# usbshare_0_2.net
KiCad netlist of a schematic drawn in EAGLE
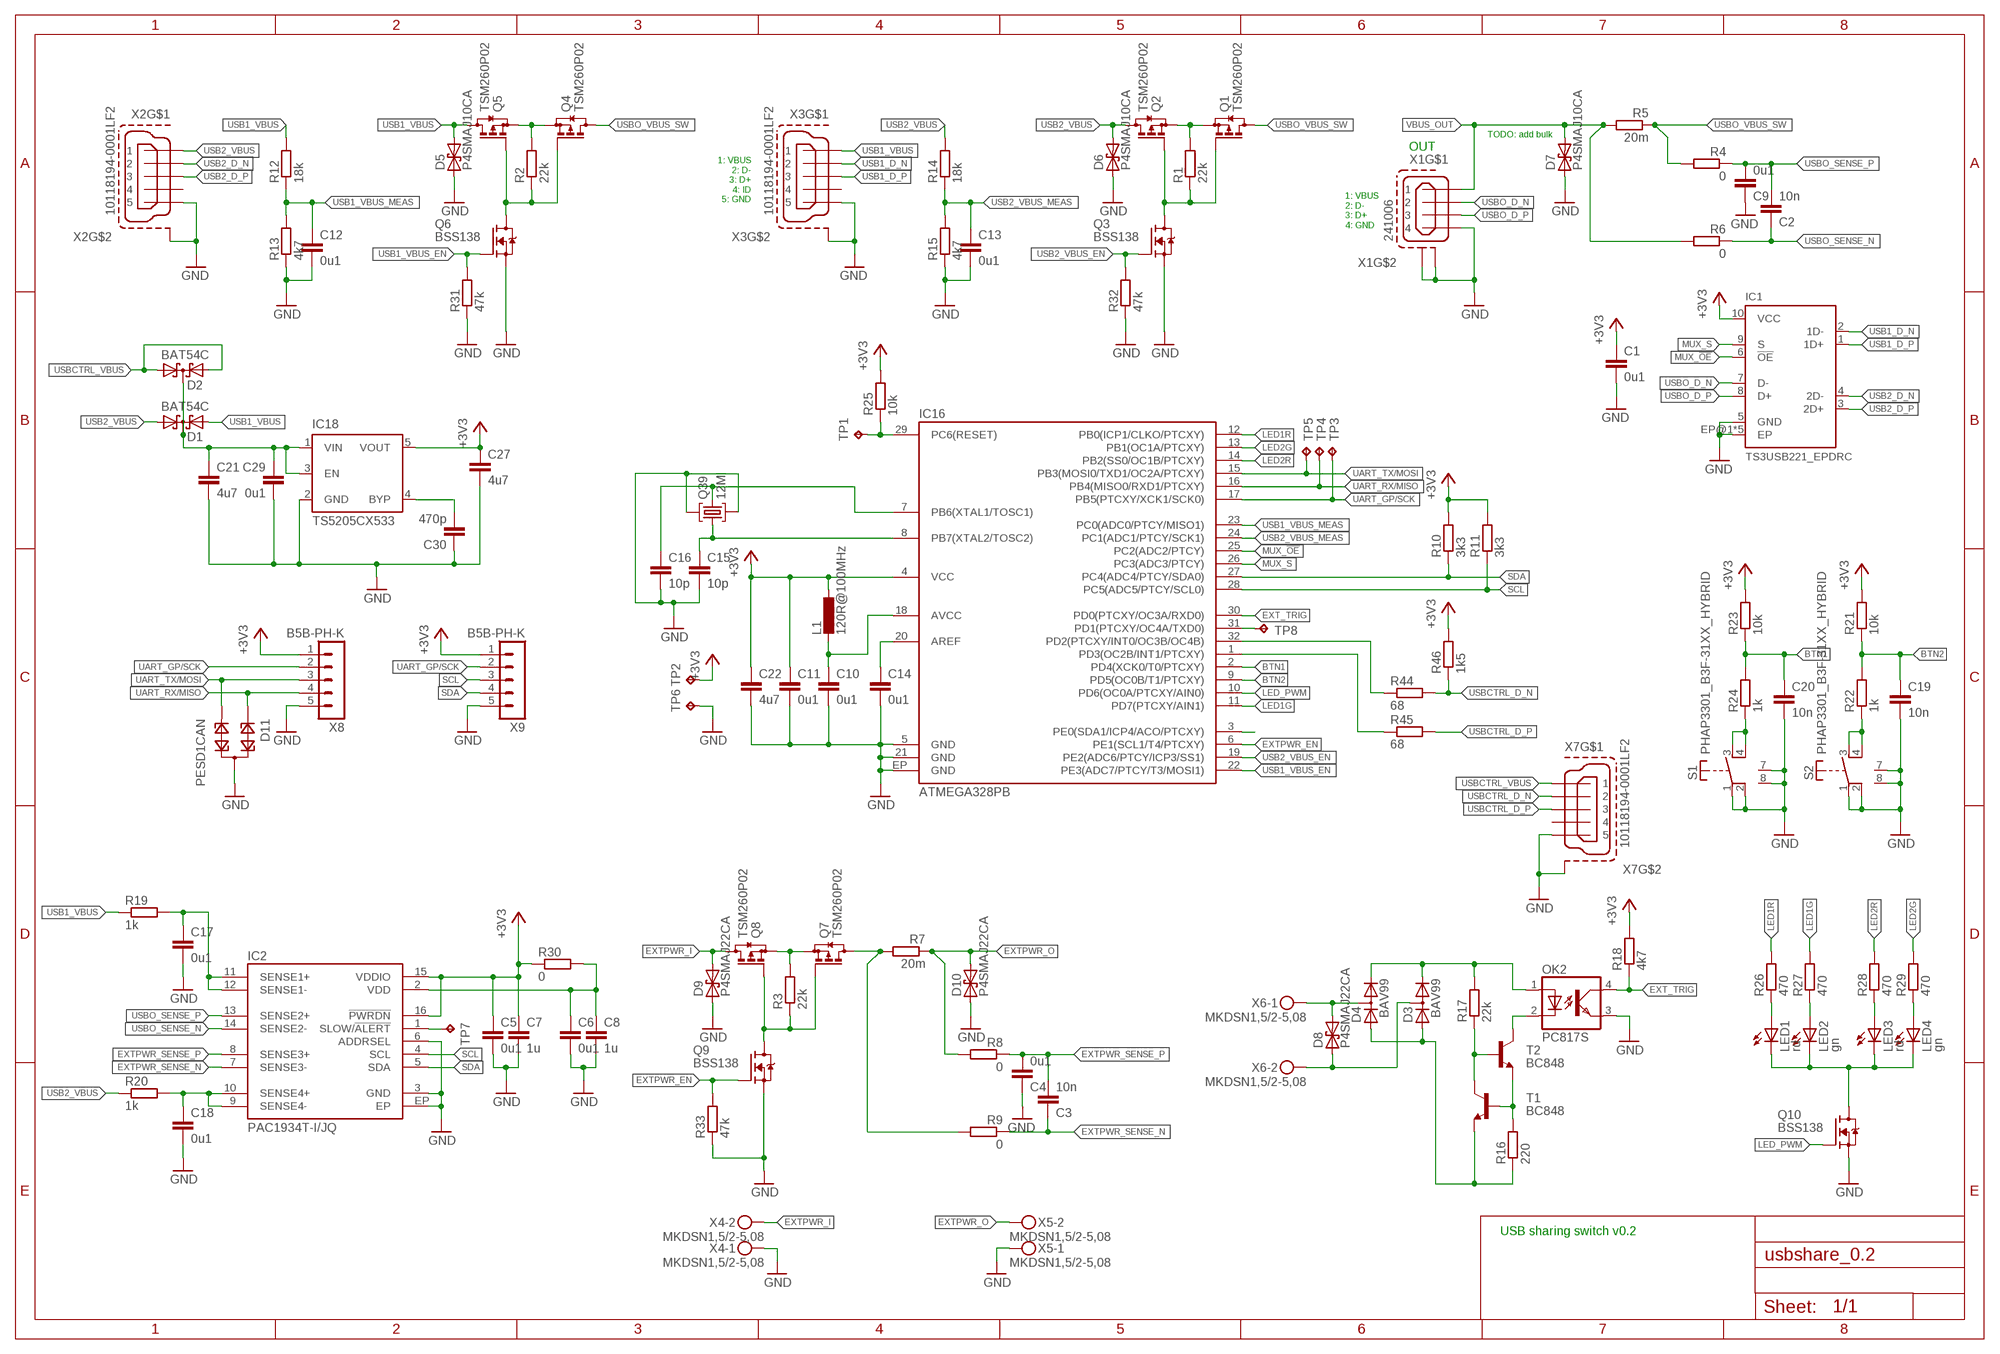
[diagram p0: schematic, sheet 1]

(export (version "E")
  (design (tool "Eeschema 10.0.6"))
  (components
    (comp (ref "C1")
      (value "0u1")
      (footprint "eagle-import:C0402")
      (libsource (lib "eagle-import") (part "C-EUC0402"))
    )
    (comp (ref "C2")
      (value "10n")
      (footprint "eagle-import:C0603")
      (libsource (lib "eagle-import") (part "C-EUC0603"))
    )
    (comp (ref "C3")
      (value "10n")
      (footprint "eagle-import:C0603")
      (libsource (lib "eagle-import") (part "C-EUC0603"))
    )
    (comp (ref "C4")
      (value "0u1")
      (footprint "eagle-import:C0603")
      (libsource (lib "eagle-import") (part "C-EUC0603"))
    )
    (comp (ref "C5")
      (value "0u1")
      (footprint "eagle-import:C0402")
      (libsource (lib "eagle-import") (part "C-EUC0402"))
    )
    (comp (ref "C6")
      (value "0u1")
      (footprint "eagle-import:C0402")
      (libsource (lib "eagle-import") (part "C-EUC0402"))
    )
    (comp (ref "C7")
      (value "1u")
      (footprint "eagle-import:C0603")
      (libsource (lib "eagle-import") (part "C-EUC0603"))
    )
    (comp (ref "C8")
      (value "1u")
      (footprint "eagle-import:C0603")
      (libsource (lib "eagle-import") (part "C-EUC0603"))
    )
    (comp (ref "C9")
      (value "0u1")
      (footprint "eagle-import:C0603")
      (libsource (lib "eagle-import") (part "C-EUC0603"))
    )
    (comp (ref "C10")
      (value "0u1")
      (footprint "eagle-import:C0402")
      (libsource (lib "eagle-import") (part "C-EUC0402"))
    )
    (comp (ref "C11")
      (value "0u1")
      (footprint "eagle-import:C0402")
      (libsource (lib "eagle-import") (part "C-EUC0402"))
    )
    (comp (ref "C12")
      (value "0u1")
      (footprint "eagle-import:C0603")
      (libsource (lib "eagle-import") (part "C-EUC0603"))
    )
    (comp (ref "C13")
      (value "0u1")
      (footprint "eagle-import:C0603")
      (libsource (lib "eagle-import") (part "C-EUC0603"))
    )
    (comp (ref "C14")
      (value "0u1")
      (footprint "eagle-import:C0402")
      (libsource (lib "eagle-import") (part "C-EUC0402"))
    )
    (comp (ref "C15")
      (value "10p")
      (footprint "eagle-import:C0603")
      (libsource (lib "eagle-import") (part "C-EUC0603"))
    )
    (comp (ref "C16")
      (value "10p")
      (footprint "eagle-import:C0603")
      (libsource (lib "eagle-import") (part "C-EUC0603"))
    )
    (comp (ref "C17")
      (value "0u1")
      (footprint "eagle-import:C0603")
      (libsource (lib "eagle-import") (part "C-EUC0603"))
    )
    (comp (ref "C18")
      (value "0u1")
      (footprint "eagle-import:C0603")
      (libsource (lib "eagle-import") (part "C-EUC0603"))
    )
    (comp (ref "C19")
      (value "10n")
      (footprint "eagle-import:C0603")
      (libsource (lib "eagle-import") (part "C-EUC0603"))
    )
    (comp (ref "C20")
      (value "10n")
      (footprint "eagle-import:C0603")
      (libsource (lib "eagle-import") (part "C-EUC0603"))
    )
    (comp (ref "C21")
      (value "4u7")
      (footprint "eagle-import:C0805")
      (libsource (lib "eagle-import") (part "C-EUC0805"))
    )
    (comp (ref "C22")
      (value "4u7")
      (footprint "eagle-import:C0603")
      (libsource (lib "eagle-import") (part "C-EUC0603"))
    )
    (comp (ref "C27")
      (value "4u7")
      (footprint "eagle-import:C0603")
      (libsource (lib "eagle-import") (part "C-EUC0603"))
    )
    (comp (ref "C29")
      (value "0u1")
      (footprint "eagle-import:C0603")
      (libsource (lib "eagle-import") (part "C-EUC0603"))
    )
    (comp (ref "C30")
      (value "470p")
      (footprint "eagle-import:C0603")
      (libsource (lib "eagle-import") (part "C-EUC0603"))
    )
    (comp (ref "D1")
      (value "BAT54C")
      (footprint "eagle-import:SOT23")
      (libsource (lib "eagle-import") (part "BAT54C"))
    )
    (comp (ref "D2")
      (value "BAT54C")
      (footprint "eagle-import:SOT23")
      (libsource (lib "eagle-import") (part "BAT54C"))
    )
    (comp (ref "D3")
      (value "BAV99")
      (footprint "eagle-import:SOT23")
      (libsource (lib "eagle-import") (part "BAV199"))
    )
    (comp (ref "D4")
      (value "BAV99")
      (footprint "eagle-import:SOT23")
      (libsource (lib "eagle-import") (part "BAV199"))
    )
    (comp (ref "D5")
      (value "P4SMAJ10CA")
      (footprint "eagle-import:DO214AC")
      (libsource (lib "eagle-import") (part "P4SMAJ10CA"))
    )
    (comp (ref "D6")
      (value "P4SMAJ10CA")
      (footprint "eagle-import:DO214AC")
      (libsource (lib "eagle-import") (part "P4SMAJ10CA"))
    )
    (comp (ref "D7")
      (value "P4SMAJ10CA")
      (footprint "eagle-import:DO214AC")
      (libsource (lib "eagle-import") (part "P4SMAJ10CA"))
    )
    (comp (ref "D8")
      (value "P4SMAJ22CA")
      (footprint "eagle-import:DO214AC")
      (libsource (lib "eagle-import") (part "P4SMAJ22CA"))
    )
    (comp (ref "D9")
      (value "P4SMAJ22CA")
      (footprint "eagle-import:DO214AC")
      (libsource (lib "eagle-import") (part "P4SMAJ22CA"))
    )
    (comp (ref "D10")
      (value "P4SMAJ22CA")
      (footprint "eagle-import:DO214AC")
      (libsource (lib "eagle-import") (part "P4SMAJ22CA"))
    )
    (comp (ref "D11")
      (value "PESD1CAN")
      (footprint "eagle-import:SOT23")
      (libsource (lib "eagle-import") (part "PESD1CAN"))
    )
    (comp (ref "IC1")
      (value "TS3USB221_EPDRC")
      (footprint "eagle-import:S-PVSON-N10")
      (libsource (lib "eagle-import") (part "TS3USB221_EPDRC"))
    )
    (comp (ref "IC2")
      (value "PAC1934T-I/JQ")
      (footprint "eagle-import:UQFN16")
      (libsource (lib "eagle-import") (part "PAC1934T-I/JQ"))
    )
    (comp (ref "IC16")
      (value "ATMEGA328PB")
      (footprint "eagle-import:VQFN32")
      (libsource (lib "eagle-import") (part "ATMEGA328PB"))
    )
    (comp (ref "IC18")
      (value "TS5205CX533")
      (footprint "eagle-import:SOT23-5")
      (libsource (lib "eagle-import") (part "TS5205CX533"))
    )
    (comp (ref "L1")
      (value "120R@100MHz")
      (footprint "eagle-import:L2012C")
      (libsource (lib "eagle-import") (part "L-EUL2012C"))
    )
    (comp (ref "LED1")
      (value "rd")
      (footprint "eagle-import:CHIP-LED0603")
      (libsource (lib "eagle-import") (part "LEDCHIP-LED0603"))
    )
    (comp (ref "LED2")
      (value "gn")
      (footprint "eagle-import:CHIP-LED0603")
      (libsource (lib "eagle-import") (part "LEDCHIP-LED0603"))
    )
    (comp (ref "LED3")
      (value "rd")
      (footprint "eagle-import:CHIP-LED0603")
      (libsource (lib "eagle-import") (part "LEDCHIP-LED0603"))
    )
    (comp (ref "LED4")
      (value "gn")
      (footprint "eagle-import:CHIP-LED0603")
      (libsource (lib "eagle-import") (part "LEDCHIP-LED0603"))
    )
    (comp (ref "OK2")
      (value "PC817S")
      (footprint "eagle-import:SMD4-9")
      (libsource (lib "eagle-import") (part "PC817S"))
    )
    (comp (ref "Q1")
      (value "TSM260P02")
      (footprint "eagle-import:SOT23")
      (libsource (lib "eagle-import") (part "BSS84"))
    )
    (comp (ref "Q2")
      (value "TSM260P02")
      (footprint "eagle-import:SOT23")
      (libsource (lib "eagle-import") (part "BSS84"))
    )
    (comp (ref "Q3")
      (value "BSS138")
      (footprint "eagle-import:SOT23")
      (libsource (lib "eagle-import") (part "BSS138"))
    )
    (comp (ref "Q4")
      (value "TSM260P02")
      (footprint "eagle-import:SOT23")
      (libsource (lib "eagle-import") (part "BSS84"))
    )
    (comp (ref "Q5")
      (value "TSM260P02")
      (footprint "eagle-import:SOT23")
      (libsource (lib "eagle-import") (part "BSS84"))
    )
    (comp (ref "Q6")
      (value "BSS138")
      (footprint "eagle-import:SOT23")
      (libsource (lib "eagle-import") (part "BSS138"))
    )
    (comp (ref "Q7")
      (value "TSM260P02")
      (footprint "eagle-import:SOT23")
      (libsource (lib "eagle-import") (part "BSS84"))
    )
    (comp (ref "Q8")
      (value "TSM260P02")
      (footprint "eagle-import:SOT23")
      (libsource (lib "eagle-import") (part "BSS84"))
    )
    (comp (ref "Q9")
      (value "BSS138")
      (footprint "eagle-import:SOT23")
      (libsource (lib "eagle-import") (part "BSS138"))
    )
    (comp (ref "Q10")
      (value "BSS138")
      (footprint "eagle-import:SOT23")
      (libsource (lib "eagle-import") (part "BSS138"))
    )
    (comp (ref "Q39")
      (value "12M")
      (footprint "eagle-import:MJ")
      (libsource (lib "eagle-import") (part "SMD4PADMJ"))
    )
    (comp (ref "R1")
      (value "22k")
      (footprint "eagle-import:R0603")
      (libsource (lib "eagle-import") (part "R-EU_R0603"))
    )
    (comp (ref "R2")
      (value "22k")
      (footprint "eagle-import:R0603")
      (libsource (lib "eagle-import") (part "R-EU_R0603"))
    )
    (comp (ref "R3")
      (value "22k")
      (footprint "eagle-import:R0603")
      (libsource (lib "eagle-import") (part "R-EU_R0603"))
    )
    (comp (ref "R4")
      (value "0")
      (footprint "eagle-import:R0603")
      (libsource (lib "eagle-import") (part "R-EU_R0603"))
    )
    (comp (ref "R5")
      (value "20m")
      (footprint "eagle-import:R0603")
      (libsource (lib "eagle-import") (part "R-EU_R0603"))
    )
    (comp (ref "R6")
      (value "0")
      (footprint "eagle-import:R0603")
      (libsource (lib "eagle-import") (part "R-EU_R0603"))
    )
    (comp (ref "R7")
      (value "20m")
      (footprint "eagle-import:R0603")
      (libsource (lib "eagle-import") (part "R-EU_R0603"))
    )
    (comp (ref "R8")
      (value "0")
      (footprint "eagle-import:R0603")
      (libsource (lib "eagle-import") (part "R-EU_R0603"))
    )
    (comp (ref "R9")
      (value "0")
      (footprint "eagle-import:R0603")
      (libsource (lib "eagle-import") (part "R-EU_R0603"))
    )
    (comp (ref "R10")
      (value "3k3")
      (footprint "eagle-import:R0603")
      (libsource (lib "eagle-import") (part "R-EU_R0603"))
    )
    (comp (ref "R11")
      (value "3k3")
      (footprint "eagle-import:R0603")
      (libsource (lib "eagle-import") (part "R-EU_R0603"))
    )
    (comp (ref "R12")
      (value "18k")
      (footprint "eagle-import:R0603")
      (libsource (lib "eagle-import") (part "R-EU_R0603"))
    )
    (comp (ref "R13")
      (value "4k7")
      (footprint "eagle-import:R0603")
      (libsource (lib "eagle-import") (part "R-EU_R0603"))
    )
    (comp (ref "R14")
      (value "18k")
      (footprint "eagle-import:R0603")
      (libsource (lib "eagle-import") (part "R-EU_R0603"))
    )
    (comp (ref "R15")
      (value "4k7")
      (footprint "eagle-import:R0603")
      (libsource (lib "eagle-import") (part "R-EU_R0603"))
    )
    (comp (ref "R16")
      (value "220")
      (footprint "eagle-import:R0603")
      (libsource (lib "eagle-import") (part "R-EU_R0603"))
    )
    (comp (ref "R17")
      (value "22k")
      (footprint "eagle-import:R0603")
      (libsource (lib "eagle-import") (part "R-EU_R0603"))
    )
    (comp (ref "R18")
      (value "4k7")
      (footprint "eagle-import:R0603")
      (libsource (lib "eagle-import") (part "R-EU_R0603"))
    )
    (comp (ref "R19")
      (value "1k")
      (footprint "eagle-import:R0603")
      (libsource (lib "eagle-import") (part "R-EU_R0603"))
    )
    (comp (ref "R20")
      (value "1k")
      (footprint "eagle-import:R0603")
      (libsource (lib "eagle-import") (part "R-EU_R0603"))
    )
    (comp (ref "R21")
      (value "10k")
      (footprint "eagle-import:R0603")
      (libsource (lib "eagle-import") (part "R-EU_R0603"))
    )
    (comp (ref "R22")
      (value "1k")
      (footprint "eagle-import:R0603")
      (libsource (lib "eagle-import") (part "R-EU_R0603"))
    )
    (comp (ref "R23")
      (value "10k")
      (footprint "eagle-import:R0603")
      (libsource (lib "eagle-import") (part "R-EU_R0603"))
    )
    (comp (ref "R24")
      (value "1k")
      (footprint "eagle-import:R0603")
      (libsource (lib "eagle-import") (part "R-EU_R0603"))
    )
    (comp (ref "R25")
      (value "10k")
      (footprint "eagle-import:R0603")
      (libsource (lib "eagle-import") (part "R-EU_R0603"))
    )
    (comp (ref "R26")
      (value "470")
      (footprint "eagle-import:R0603")
      (libsource (lib "eagle-import") (part "R-EU_R0603"))
    )
    (comp (ref "R27")
      (value "470")
      (footprint "eagle-import:R0603")
      (libsource (lib "eagle-import") (part "R-EU_R0603"))
    )
    (comp (ref "R28")
      (value "470")
      (footprint "eagle-import:R0603")
      (libsource (lib "eagle-import") (part "R-EU_R0603"))
    )
    (comp (ref "R29")
      (value "470")
      (footprint "eagle-import:R0603")
      (libsource (lib "eagle-import") (part "R-EU_R0603"))
    )
    (comp (ref "R30")
      (value "0")
      (footprint "eagle-import:R0603")
      (libsource (lib "eagle-import") (part "R-EU_R0603"))
    )
    (comp (ref "R31")
      (value "47k")
      (footprint "eagle-import:R0402")
      (libsource (lib "eagle-import") (part "R-EU_R0402"))
    )
    (comp (ref "R32")
      (value "47k")
      (footprint "eagle-import:R0402")
      (libsource (lib "eagle-import") (part "R-EU_R0402"))
    )
    (comp (ref "R33")
      (value "47k")
      (footprint "eagle-import:R0402")
      (libsource (lib "eagle-import") (part "R-EU_R0402"))
    )
    (comp (ref "R44")
      (value "68")
      (footprint "eagle-import:R0603")
      (libsource (lib "eagle-import") (part "R-EU_R0603"))
    )
    (comp (ref "R45")
      (value "68")
      (footprint "eagle-import:R0603")
      (libsource (lib "eagle-import") (part "R-EU_R0603"))
    )
    (comp (ref "R46")
      (value "1k5")
      (footprint "eagle-import:R0402")
      (libsource (lib "eagle-import") (part "R-EU_R0402"))
    )
    (comp (ref "S1")
      (value "PHAP3301_B3F-31XX_HYBRID")
      (footprint "eagle-import:PHAP3301_B3F-31XX_HYBRID")
      (libsource (lib "eagle-import") (part "PHAP3301_B3F-31XX_HYBRID"))
    )
    (comp (ref "S2")
      (value "PHAP3301_B3F-31XX_HYBRID")
      (footprint "eagle-import:PHAP3301_B3F-31XX_HYBRID")
      (libsource (lib "eagle-import") (part "PHAP3301_B3F-31XX_HYBRID"))
    )
    (comp (ref "T1")
      (value "BC848")
      (footprint "eagle-import:SOT23")
      (libsource (lib "eagle-import") (part "BC848"))
    )
    (comp (ref "T2")
      (value "BC848")
      (footprint "eagle-import:SOT23")
      (libsource (lib "eagle-import") (part "BC848"))
    )
    (comp (ref "TP1")
      (value "TPTP13R")
      (footprint "eagle-import:TP13R")
      (libsource (lib "eagle-import") (part "TPTP13R"))
    )
    (comp (ref "TP2")
      (value "TPTP13R")
      (footprint "eagle-import:TP13R")
      (libsource (lib "eagle-import") (part "TPTP13R"))
    )
    (comp (ref "TP3")
      (value "TPTP13R")
      (footprint "eagle-import:TP13R")
      (libsource (lib "eagle-import") (part "TPTP13R"))
    )
    (comp (ref "TP4")
      (value "TPTP13R")
      (footprint "eagle-import:TP13R")
      (libsource (lib "eagle-import") (part "TPTP13R"))
    )
    (comp (ref "TP5")
      (value "TPTP13R")
      (footprint "eagle-import:TP13R")
      (libsource (lib "eagle-import") (part "TPTP13R"))
    )
    (comp (ref "TP6")
      (value "TPTP13R")
      (footprint "eagle-import:TP13R")
      (libsource (lib "eagle-import") (part "TPTP13R"))
    )
    (comp (ref "TP7")
      (value "TPTP13R")
      (footprint "eagle-import:TP13R")
      (libsource (lib "eagle-import") (part "TPTP13R"))
    )
    (comp (ref "TP8")
      (value "TPTP13R")
      (footprint "eagle-import:TP13R")
      (libsource (lib "eagle-import") (part "TPTP13R"))
    )
    (comp (ref "X1")
      (value "241006")
      (footprint "eagle-import:241006")
      (fields (field (name "OC_REICHELT") "LUM 2410-06"))
      (libsource (lib "eagle-import") (part "241006"))
    )
    (comp (ref "X2")
      (value "10118194-0001LF2")
      (footprint "eagle-import:10118194-0001LF_2")
      (libsource (lib "eagle-import") (part "10118194-0001LF2"))
    )
    (comp (ref "X3")
      (value "10118194-0001LF2")
      (footprint "eagle-import:10118194-0001LF_2")
      (libsource (lib "eagle-import") (part "10118194-0001LF2"))
    )
    (comp (ref "X4")
      (value "MKDSN1,5/2-5,08")
      (footprint "eagle-import:MKDSN1,5_2-5,08")
      (fields (field (name "OC_REICHELT") "AKL 101-02"))
      (libsource (lib "eagle-import") (part "MKDSN1,5/2-5,08"))
    )
    (comp (ref "X5")
      (value "MKDSN1,5/2-5,08")
      (footprint "eagle-import:MKDSN1,5_2-5,08")
      (fields (field (name "OC_REICHELT") "AKL 101-02"))
      (libsource (lib "eagle-import") (part "MKDSN1,5/2-5,08"))
    )
    (comp (ref "X6")
      (value "MKDSN1,5/2-5,08")
      (footprint "eagle-import:MKDSN1,5_2-5,08")
      (fields (field (name "OC_REICHELT") "AKL 101-02"))
      (libsource (lib "eagle-import") (part "MKDSN1,5/2-5,08"))
    )
    (comp (ref "X7")
      (value "10118194-0001LF2")
      (footprint "eagle-import:10118194-0001LF_2")
      (libsource (lib "eagle-import") (part "10118194-0001LF2"))
    )
    (comp (ref "X8")
      (value "B5B-PH-K")
      (footprint "eagle-import:B5B-PH-K")
      (libsource (lib "eagle-import") (part "B5B-PH-K"))
    )
    (comp (ref "X9")
      (value "B5B-PH-K")
      (footprint "eagle-import:B5B-PH-K")
      (libsource (lib "eagle-import") (part "B5B-PH-K"))
    )
  )
  (nets
    (net (code "1") (name "+3V3") (class "Default")
      (node (ref "C1") (pin "1") (pinfunction "1_1") (pintype "passive"))
      (node (ref "C11") (pin "1") (pinfunction "1_1") (pintype "passive"))
      (node (ref "C22") (pin "1") (pinfunction "1_1") (pintype "passive"))
      (node (ref "C27") (pin "1") (pinfunction "1_1") (pintype "passive"))
      (node (ref "C5") (pin "1") (pinfunction "1_1") (pintype "passive"))
      (node (ref "C7") (pin "1") (pinfunction "1_1") (pintype "passive"))
      (node (ref "IC1") (pin "10") (pinfunction "VCC_10") (pintype "power_in"))
      (node (ref "IC16") (pin "4") (pinfunction "VCC_4") (pintype "power_in"))
      (node (ref "IC18") (pin "5") (pinfunction "VOUT_5") (pintype "passive"))
      (node (ref "IC2") (pin "15") (pinfunction "VDDIO_15") (pintype "power_in"))
      (node (ref "IC2") (pin "16") (pinfunction "~{PWRDN}_16") (pintype "input"))
      (node (ref "L1") (pin "1") (pinfunction "1_1") (pintype "passive"))
      (node (ref "R10") (pin "2") (pinfunction "2_2") (pintype "passive"))
      (node (ref "R11") (pin "2") (pinfunction "2_2") (pintype "passive"))
      (node (ref "R18") (pin "2") (pinfunction "2_2") (pintype "passive"))
      (node (ref "R21") (pin "2") (pinfunction "2_2") (pintype "passive"))
      (node (ref "R23") (pin "2") (pinfunction "2_2") (pintype "passive"))
      (node (ref "R25") (pin "2") (pinfunction "2_2") (pintype "passive"))
      (node (ref "R30") (pin "1") (pinfunction "1_1") (pintype "passive"))
      (node (ref "R46") (pin "2") (pinfunction "2_2") (pintype "passive"))
      (node (ref "TP2") (pin "TP") (pinfunction "TP_TP") (pintype "input"))
      (node (ref "X8") (pin "1") (pinfunction "1_1") (pintype "passive"))
      (node (ref "X9") (pin "1") (pinfunction "1_1") (pintype "passive"))
    )
    (net (code "2") (name "/MUX_~{OE}") (class "Default")
      (node (ref "IC1") (pin "6") (pinfunction "~{OE}_6") (pintype "input"))
      (node (ref "IC16") (pin "25") (pinfunction "PC2(ADC2/PTCY)_25") (pintype "bidirectional"))
    )
    (net (code "3") (name "BTN1") (class "Default")
      (node (ref "C20") (pin "1") (pinfunction "1_1") (pintype "passive"))
      (node (ref "IC16") (pin "2") (pinfunction "PD4(XCK0/T0/PTCXY)_2") (pintype "bidirectional"))
      (node (ref "R23") (pin "1") (pinfunction "1_1") (pintype "passive"))
      (node (ref "R24") (pin "2") (pinfunction "2_2") (pintype "passive"))
    )
    (net (code "4") (name "BTN2") (class "Default")
      (node (ref "C19") (pin "1") (pinfunction "1_1") (pintype "passive"))
      (node (ref "IC16") (pin "9") (pinfunction "PD5(OC0B/T1/PTCXY)_9") (pintype "bidirectional"))
      (node (ref "R21") (pin "1") (pinfunction "1_1") (pintype "passive"))
      (node (ref "R22") (pin "2") (pinfunction "2_2") (pintype "passive"))
    )
    (net (code "5") (name "EXTPWR_EN") (class "Default")
      (node (ref "IC16") (pin "6") (pinfunction "PE1(SCL1/T4/PTCXY)_6") (pintype "bidirectional"))
      (node (ref "Q9") (pin "1") (pinfunction "G_1") (pintype "passive"))
      (node (ref "R33") (pin "2") (pinfunction "2_2") (pintype "passive"))
    )
    (net (code "6") (name "EXTPWR_I") (class "Default")
      (node (ref "D9") (pin "2") (pinfunction "2_2") (pintype "passive"))
      (node (ref "Q8") (pin "3") (pinfunction "D_3") (pintype "passive"))
      (node (ref "X4") (pin "2") (pinfunction "KL_2") (pintype "passive"))
    )
    (net (code "7") (name "EXTPWR_O") (class "Default")
      (node (ref "D10") (pin "2") (pinfunction "2_2") (pintype "passive"))
      (node (ref "R7") (pin "1") (pinfunction "1_1") (pintype "passive"))
      (node (ref "R8") (pin "2") (pinfunction "2_2") (pintype "passive"))
      (node (ref "X5") (pin "2") (pinfunction "KL_2") (pintype "passive"))
    )
    (net (code "8") (name "EXTPWR_SENSE_N") (class "Default")
      (node (ref "C3") (pin "1") (pinfunction "1_1") (pintype "passive"))
      (node (ref "IC2") (pin "7") (pinfunction "SENSE3-_7") (pintype "input"))
      (node (ref "R9") (pin "1") (pinfunction "1_1") (pintype "passive"))
    )
    (net (code "9") (name "EXTPWR_SENSE_P") (class "Default")
      (node (ref "C3") (pin "2") (pinfunction "2_2") (pintype "passive"))
      (node (ref "C4") (pin "2") (pinfunction "2_2") (pintype "passive"))
      (node (ref "IC2") (pin "8") (pinfunction "SENSE3+_8") (pintype "input"))
      (node (ref "R8") (pin "1") (pinfunction "1_1") (pintype "passive"))
    )
    (net (code "10") (name "EXT_TRIG") (class "Default")
      (node (ref "IC16") (pin "30") (pinfunction "PD0(PTCXY/OC3A/RXD0)_30") (pintype "bidirectional"))
      (node (ref "OK2") (pin "4") (pinfunction "COL_4") (pintype "passive"))
      (node (ref "R18") (pin "1") (pinfunction "1_1") (pintype "passive"))
    )
    (net (code "11") (name "GND") (class "Default")
      (node (ref "C1") (pin "2") (pinfunction "2_2") (pintype "passive"))
      (node (ref "C10") (pin "2") (pinfunction "2_2") (pintype "passive"))
      (node (ref "C11") (pin "2") (pinfunction "2_2") (pintype "passive"))
      (node (ref "C12") (pin "2") (pinfunction "2_2") (pintype "passive"))
      (node (ref "C13") (pin "2") (pinfunction "2_2") (pintype "passive"))
      (node (ref "C14") (pin "2") (pinfunction "2_2") (pintype "passive"))
      (node (ref "C15") (pin "2") (pinfunction "2_2") (pintype "passive"))
      (node (ref "C16") (pin "2") (pinfunction "2_2") (pintype "passive"))
      (node (ref "C17") (pin "2") (pinfunction "2_2") (pintype "passive"))
      (node (ref "C18") (pin "2") (pinfunction "2_2") (pintype "passive"))
      (node (ref "C19") (pin "2") (pinfunction "2_2") (pintype "passive"))
      (node (ref "C20") (pin "2") (pinfunction "2_2") (pintype "passive"))
      (node (ref "C21") (pin "2") (pinfunction "2_2") (pintype "passive"))
      (node (ref "C22") (pin "2") (pinfunction "2_2") (pintype "passive"))
      (node (ref "C27") (pin "2") (pinfunction "2_2") (pintype "passive"))
      (node (ref "C29") (pin "2") (pinfunction "2_2") (pintype "passive"))
      (node (ref "C30") (pin "1") (pinfunction "1_1") (pintype "passive"))
      (node (ref "C4") (pin "1") (pinfunction "1_1") (pintype "passive"))
      (node (ref "C5") (pin "2") (pinfunction "2_2") (pintype "passive"))
      (node (ref "C6") (pin "2") (pinfunction "2_2") (pintype "passive"))
      (node (ref "C7") (pin "2") (pinfunction "2_2") (pintype "passive"))
      (node (ref "C8") (pin "2") (pinfunction "2_2") (pintype "passive"))
      (node (ref "C9") (pin "1") (pinfunction "1_1") (pintype "passive"))
      (node (ref "D10") (pin "1") (pinfunction "1_1") (pintype "passive"))
      (node (ref "D11") (pin "3") (pinfunction "3_3") (pintype "passive"))
      (node (ref "D5") (pin "1") (pinfunction "1_1") (pintype "passive"))
      (node (ref "D6") (pin "1") (pinfunction "1_1") (pintype "passive"))
      (node (ref "D7") (pin "1") (pinfunction "1_1") (pintype "passive"))
      (node (ref "D9") (pin "1") (pinfunction "1_1") (pintype "passive"))
      (node (ref "IC1") (pin "5") (pinfunction "GND_5") (pintype "power_in"))
      (node (ref "IC1") (pin "EP@1") (pinfunction "EP_EP@1") (pintype "power_in"))
      (node (ref "IC1") (pin "EP@2") (pinfunction "EP_EP@2") (pintype "power_in"))
      (node (ref "IC1") (pin "EP@3") (pinfunction "EP_EP@3") (pintype "power_in"))
      (node (ref "IC1") (pin "EP@4") (pinfunction "EP_EP@4") (pintype "power_in"))
      (node (ref "IC1") (pin "EP@5") (pinfunction "EP_EP@5") (pintype "power_in"))
      (node (ref "IC16") (pin "21") (pinfunction "GND_21") (pintype "power_in"))
      (node (ref "IC16") (pin "5") (pinfunction "GND_5") (pintype "power_in"))
      (node (ref "IC16") (pin "EP") (pinfunction "GND_EP") (pintype "power_in"))
      (node (ref "IC18") (pin "2") (pinfunction "GND_2") (pintype "power_in"))
      (node (ref "IC2") (pin "3") (pinfunction "GND_3") (pintype "power_in"))
      (node (ref "IC2") (pin "6") (pinfunction "ADDRSEL_6") (pintype "bidirectional"))
      (node (ref "IC2") (pin "EP") (pinfunction "EP_EP") (pintype "power_in"))
      (node (ref "OK2") (pin "3") (pinfunction "EMIT_3") (pintype "passive"))
      (node (ref "Q10") (pin "2") (pinfunction "S_2") (pintype "passive"))
      (node (ref "Q3") (pin "2") (pinfunction "S_2") (pintype "passive"))
      (node (ref "Q39") (pin "2") (pinfunction "2_2") (pintype "passive"))
      (node (ref "Q39") (pin "4") (pinfunction "4_4") (pintype "passive"))
      (node (ref "Q6") (pin "2") (pinfunction "S_2") (pintype "passive"))
      (node (ref "Q9") (pin "2") (pinfunction "S_2") (pintype "passive"))
      (node (ref "R13") (pin "1") (pinfunction "1_1") (pintype "passive"))
      (node (ref "R15") (pin "1") (pinfunction "1_1") (pintype "passive"))
      (node (ref "R31") (pin "1") (pinfunction "1_1") (pintype "passive"))
      (node (ref "R32") (pin "1") (pinfunction "1_1") (pintype "passive"))
      (node (ref "R33") (pin "1") (pinfunction "1_1") (pintype "passive"))
      (node (ref "S1") (pin "1") (pinfunction "P_1") (pintype "passive"))
      (node (ref "S1") (pin "2") (pinfunction "P1_2") (pintype "passive"))
      (node (ref "S1") (pin "7") (pinfunction "M1_7") (pintype "passive"))
      (node (ref "S1") (pin "8") (pinfunction "M2_8") (pintype "passive"))
      (node (ref "S2") (pin "1") (pinfunction "P_1") (pintype "passive"))
      (node (ref "S2") (pin "2") (pinfunction "P1_2") (pintype "passive"))
      (node (ref "S2") (pin "7") (pinfunction "M1_7") (pintype "passive"))
      (node (ref "S2") (pin "8") (pinfunction "M2_8") (pintype "passive"))
      (node (ref "TP6") (pin "TP") (pinfunction "TP_TP") (pintype "input"))
      (node (ref "X1") (pin "4") (pinfunction "4_4") (pintype "passive"))
      (node (ref "X1") (pin "5") (pinfunction "S1_5") (pintype "passive"))
      (node (ref "X1") (pin "6") (pinfunction "S2_6") (pintype "passive"))
      (node (ref "X2") (pin "5") (pinfunction "5_5") (pintype "input"))
      (node (ref "X2") (pin "S1") (pinfunction "S1_S1") (pintype "passive"))
      (node (ref "X2") (pin "S2") (pinfunction "S1_S2") (pintype "passive"))
      (node (ref "X2") (pin "S3") (pinfunction "S1_S3") (pintype "passive"))
      (node (ref "X2") (pin "S4") (pinfunction "S1_S4") (pintype "passive"))
      (node (ref "X2") (pin "S5") (pinfunction "S1_S5") (pintype "passive"))
      (node (ref "X2") (pin "S6") (pinfunction "S1_S6") (pintype "passive"))
      (node (ref "X3") (pin "5") (pinfunction "5_5") (pintype "input"))
      (node (ref "X3") (pin "S1") (pinfunction "S1_S1") (pintype "passive"))
      (node (ref "X3") (pin "S2") (pinfunction "S1_S2") (pintype "passive"))
      (node (ref "X3") (pin "S3") (pinfunction "S1_S3") (pintype "passive"))
      (node (ref "X3") (pin "S4") (pinfunction "S1_S4") (pintype "passive"))
      (node (ref "X3") (pin "S5") (pinfunction "S1_S5") (pintype "passive"))
      (node (ref "X3") (pin "S6") (pinfunction "S1_S6") (pintype "passive"))
      (node (ref "X4") (pin "1") (pinfunction "KL_1") (pintype "passive"))
      (node (ref "X5") (pin "1") (pinfunction "KL_1") (pintype "passive"))
      (node (ref "X7") (pin "5") (pinfunction "5_5") (pintype "input"))
      (node (ref "X7") (pin "S1") (pinfunction "S1_S1") (pintype "passive"))
      (node (ref "X7") (pin "S2") (pinfunction "S1_S2") (pintype "passive"))
      (node (ref "X7") (pin "S3") (pinfunction "S1_S3") (pintype "passive"))
      (node (ref "X7") (pin "S4") (pinfunction "S1_S4") (pintype "passive"))
      (node (ref "X7") (pin "S5") (pinfunction "S1_S5") (pintype "passive"))
      (node (ref "X7") (pin "S6") (pinfunction "S1_S6") (pintype "passive"))
      (node (ref "X8") (pin "5") (pinfunction "5_5") (pintype "passive"))
      (node (ref "X9") (pin "5") (pinfunction "5_5") (pintype "passive"))
    )
    (net (code "12") (name "LED1G") (class "Default")
      (node (ref "IC16") (pin "11") (pinfunction "PD7(PTCXY/AIN1)_11") (pintype "bidirectional"))
      (node (ref "R27") (pin "2") (pinfunction "2_2") (pintype "passive"))
    )
    (net (code "13") (name "LED1R") (class "Default")
      (node (ref "IC16") (pin "12") (pinfunction "PB0(ICP1/CLKO/PTCXY)_12") (pintype "bidirectional"))
      (node (ref "R26") (pin "2") (pinfunction "2_2") (pintype "passive"))
    )
    (net (code "14") (name "LED2G") (class "Default")
      (node (ref "IC16") (pin "13") (pinfunction "PB1(OC1A/PTCXY)_13") (pintype "bidirectional"))
      (node (ref "R29") (pin "2") (pinfunction "2_2") (pintype "passive"))
    )
    (net (code "15") (name "LED2R") (class "Default")
      (node (ref "IC16") (pin "14") (pinfunction "PB2(SS0/OC1B/PTCXY)_14") (pintype "bidirectional"))
      (node (ref "R28") (pin "2") (pinfunction "2_2") (pintype "passive"))
    )
    (net (code "16") (name "LED_PWM") (class "Default")
      (node (ref "IC16") (pin "10") (pinfunction "PD6(OC0A/PTCXY/AIN0)_10") (pintype "bidirectional"))
      (node (ref "Q10") (pin "1") (pinfunction "G_1") (pintype "passive"))
    )
    (net (code "17") (name "MUX_S") (class "Default")
      (node (ref "IC1") (pin "9") (pinfunction "S_9") (pintype "input"))
      (node (ref "IC16") (pin "26") (pinfunction "PC3(ADC3/PTCY)_26") (pintype "bidirectional"))
    )
    (net (code "18") (name "Net-(D1-CC)") (class "Default")
      (node (ref "C21") (pin "1") (pinfunction "1_1") (pintype "passive"))
      (node (ref "C29") (pin "1") (pinfunction "1_1") (pintype "passive"))
      (node (ref "D1") (pin "3") (pinfunction "CC_3") (pintype "passive"))
      (node (ref "D2") (pin "3") (pinfunction "CC_3") (pintype "passive"))
      (node (ref "IC18") (pin "1") (pinfunction "VIN_1") (pintype "input"))
      (node (ref "IC18") (pin "3") (pinfunction "EN_3") (pintype "input"))
    )
    (net (code "19") (name "Net-(D3-A)") (class "Default")
      (node (ref "D3") (pin "1") (pinfunction "A_1") (pintype "passive"))
      (node (ref "D4") (pin "1") (pinfunction "A_1") (pintype "passive"))
      (node (ref "R16") (pin "1") (pinfunction "1_1") (pintype "passive"))
      (node (ref "T1") (pin "2") (pinfunction "E_2") (pintype "passive"))
    )
    (net (code "20") (name "Net-(D3-AC)") (class "Default")
      (node (ref "D3") (pin "3") (pinfunction "AC_3") (pintype "passive"))
      (node (ref "D8") (pin "1") (pinfunction "1_1") (pintype "passive"))
      (node (ref "X6") (pin "2") (pinfunction "KL_2") (pintype "passive"))
    )
    (net (code "21") (name "Net-(D3-C)") (class "Default")
      (node (ref "D3") (pin "2") (pinfunction "C_2") (pintype "passive"))
      (node (ref "D4") (pin "2") (pinfunction "C_2") (pintype "passive"))
      (node (ref "OK2") (pin "1") (pinfunction "A_1") (pintype "passive"))
      (node (ref "R17") (pin "2") (pinfunction "2_2") (pintype "passive"))
    )
    (net (code "22") (name "Net-(D4-AC)") (class "Default")
      (node (ref "D4") (pin "3") (pinfunction "AC_3") (pintype "passive"))
      (node (ref "D8") (pin "2") (pinfunction "2_2") (pintype "passive"))
      (node (ref "X6") (pin "1") (pinfunction "KL_1") (pintype "passive"))
    )
    (net (code "23") (name "Net-(IC2-SENSE1+)") (class "Default")
      (node (ref "C17") (pin "1") (pinfunction "1_1") (pintype "passive"))
      (node (ref "IC2") (pin "11") (pinfunction "SENSE1+_11") (pintype "input"))
      (node (ref "IC2") (pin "12") (pinfunction "SENSE1-_12") (pintype "input"))
      (node (ref "R19") (pin "2") (pinfunction "2_2") (pintype "passive"))
    )
    (net (code "24") (name "Net-(IC2-SENSE4+)") (class "Default")
      (node (ref "C18") (pin "1") (pinfunction "1_1") (pintype "passive"))
      (node (ref "IC2") (pin "10") (pinfunction "SENSE4+_10") (pintype "input"))
      (node (ref "IC2") (pin "9") (pinfunction "SENSE4-_9") (pintype "input"))
      (node (ref "R20") (pin "2") (pinfunction "2_2") (pintype "passive"))
    )
    (net (code "25") (name "Net-(IC2-SLOW{slash}~{ALERT})") (class "Default")
      (node (ref "IC2") (pin "1") (pinfunction "SLOW/~{ALERT}_1") (pintype "bidirectional"))
      (node (ref "TP7") (pin "TP") (pinfunction "TP_TP") (pintype "input"))
    )
    (net (code "26") (name "Net-(IC2-VDD)") (class "Default")
      (node (ref "C6") (pin "1") (pinfunction "1_1") (pintype "passive"))
      (node (ref "C8") (pin "1") (pinfunction "1_1") (pintype "passive"))
      (node (ref "IC2") (pin "2") (pinfunction "VDD_2") (pintype "power_in"))
      (node (ref "R30") (pin "2") (pinfunction "2_2") (pintype "passive"))
    )
    (net (code "27") (name "Net-(IC16-AREF)") (class "Default")
      (node (ref "C14") (pin "1") (pinfunction "1_1") (pintype "passive"))
      (node (ref "IC16") (pin "20") (pinfunction "AREF_20") (pintype "power_in"))
    )
    (net (code "28") (name "Net-(IC16-AVCC)") (class "Default")
      (node (ref "C10") (pin "1") (pinfunction "1_1") (pintype "passive"))
      (node (ref "IC16") (pin "18") (pinfunction "AVCC_18") (pintype "power_in"))
      (node (ref "L1") (pin "2") (pinfunction "2_2") (pintype "passive"))
    )
    (net (code "29") (name "Net-(IC16-PB6(XTAL1{slash}TOSC1))") (class "Default")
      (node (ref "C16") (pin "1") (pinfunction "1_1") (pintype "passive"))
      (node (ref "IC16") (pin "7") (pinfunction "PB6(XTAL1/TOSC1)_7") (pintype "bidirectional"))
      (node (ref "Q39") (pin "3") (pinfunction "3_3") (pintype "passive"))
    )
    (net (code "30") (name "Net-(IC16-PB7(XTAL2{slash}TOSC2))") (class "Default")
      (node (ref "C15") (pin "1") (pinfunction "1_1") (pintype "passive"))
      (node (ref "IC16") (pin "8") (pinfunction "PB7(XTAL2/TOSC2)_8") (pintype "bidirectional"))
      (node (ref "Q39") (pin "1") (pinfunction "1_1") (pintype "passive"))
    )
    (net (code "31") (name "Net-(IC16-PC6(RESET))") (class "Default")
      (node (ref "IC16") (pin "29") (pinfunction "PC6(RESET)_29") (pintype "bidirectional"))
      (node (ref "R25") (pin "1") (pinfunction "1_1") (pintype "passive"))
      (node (ref "TP1") (pin "TP") (pinfunction "TP_TP") (pintype "input"))
    )
    (net (code "32") (name "Net-(IC16-PD1(PTCXY{slash}OC4A{slash}TXD0))") (class "Default")
      (node (ref "IC16") (pin "31") (pinfunction "PD1(PTCXY/OC4A/TXD0)_31") (pintype "bidirectional"))
      (node (ref "TP8") (pin "TP") (pinfunction "TP_TP") (pintype "input"))
    )
    (net (code "33") (name "Net-(IC16-PD2(PTCXY{slash}INT0{slash}OC3B{slash}OC4B))") (class "Default")
      (node (ref "IC16") (pin "32") (pinfunction "PD2(PTCXY/INT0/OC3B/OC4B)_32") (pintype "bidirectional"))
      (node (ref "R44") (pin "1") (pinfunction "1_1") (pintype "passive"))
    )
    (net (code "34") (name "Net-(IC16-PD3(OC2B{slash}INT1{slash}PTCXY))") (class "Default")
      (node (ref "IC16") (pin "1") (pinfunction "PD3(OC2B/INT1/PTCXY)_1") (pintype "bidirectional"))
      (node (ref "R45") (pin "1") (pinfunction "1_1") (pintype "passive"))
    )
    (net (code "35") (name "Net-(IC18-BYP)") (class "Default")
      (node (ref "C30") (pin "2") (pinfunction "2_2") (pintype "passive"))
      (node (ref "IC18") (pin "4") (pinfunction "BYP_4") (pintype "passive"))
    )
    (net (code "36") (name "Net-(LED1-PadA)") (class "Default")
      (node (ref "LED1") (pin "A") (pinfunction "A_A") (pintype "passive"))
      (node (ref "R26") (pin "1") (pinfunction "1_1") (pintype "passive"))
    )
    (net (code "37") (name "Net-(LED2-PadA)") (class "Default")
      (node (ref "LED2") (pin "A") (pinfunction "A_A") (pintype "passive"))
      (node (ref "R27") (pin "1") (pinfunction "1_1") (pintype "passive"))
    )
    (net (code "38") (name "Net-(LED3-PadA)") (class "Default")
      (node (ref "LED3") (pin "A") (pinfunction "A_A") (pintype "passive"))
      (node (ref "R28") (pin "1") (pinfunction "1_1") (pintype "passive"))
    )
    (net (code "39") (name "Net-(LED4-PadA)") (class "Default")
      (node (ref "LED4") (pin "A") (pinfunction "A_A") (pintype "passive"))
      (node (ref "R29") (pin "1") (pinfunction "1_1") (pintype "passive"))
    )
    (net (code "40") (name "Net-(OK2-C)") (class "Default")
      (node (ref "OK2") (pin "2") (pinfunction "C_2") (pintype "passive"))
      (node (ref "T2") (pin "3") (pinfunction "C_3") (pintype "passive"))
    )
    (net (code "41") (name "Net-(Q1-G)") (class "Default")
      (node (ref "Q1") (pin "1") (pinfunction "G_1") (pintype "passive"))
      (node (ref "Q2") (pin "1") (pinfunction "G_1") (pintype "passive"))
      (node (ref "Q3") (pin "3") (pinfunction "D_3") (pintype "passive"))
      (node (ref "R1") (pin "1") (pinfunction "1_1") (pintype "passive"))
    )
    (net (code "42") (name "Net-(Q1-S)") (class "Default")
      (node (ref "Q1") (pin "2") (pinfunction "S_2") (pintype "passive"))
      (node (ref "Q2") (pin "2") (pinfunction "S_2") (pintype "passive"))
      (node (ref "R1") (pin "2") (pinfunction "2_2") (pintype "passive"))
    )
    (net (code "43") (name "Net-(Q4-G)") (class "Default")
      (node (ref "Q4") (pin "1") (pinfunction "G_1") (pintype "passive"))
      (node (ref "Q5") (pin "1") (pinfunction "G_1") (pintype "passive"))
      (node (ref "Q6") (pin "3") (pinfunction "D_3") (pintype "passive"))
      (node (ref "R2") (pin "1") (pinfunction "1_1") (pintype "passive"))
    )
    (net (code "44") (name "Net-(Q4-S)") (class "Default")
      (node (ref "Q4") (pin "2") (pinfunction "S_2") (pintype "passive"))
      (node (ref "Q5") (pin "2") (pinfunction "S_2") (pintype "passive"))
      (node (ref "R2") (pin "2") (pinfunction "2_2") (pintype "passive"))
    )
    (net (code "45") (name "Net-(Q7-D)") (class "Default")
      (node (ref "Q7") (pin "3") (pinfunction "D_3") (pintype "passive"))
      (node (ref "R7") (pin "2") (pinfunction "2_2") (pintype "passive"))
      (node (ref "R9") (pin "2") (pinfunction "2_2") (pintype "passive"))
    )
    (net (code "46") (name "Net-(Q7-G)") (class "Default")
      (node (ref "Q7") (pin "1") (pinfunction "G_1") (pintype "passive"))
      (node (ref "Q8") (pin "1") (pinfunction "G_1") (pintype "passive"))
      (node (ref "Q9") (pin "3") (pinfunction "D_3") (pintype "passive"))
      (node (ref "R3") (pin "1") (pinfunction "1_1") (pintype "passive"))
    )
    (net (code "47") (name "Net-(Q7-S)") (class "Default")
      (node (ref "Q7") (pin "2") (pinfunction "S_2") (pintype "passive"))
      (node (ref "Q8") (pin "2") (pinfunction "S_2") (pintype "passive"))
      (node (ref "R3") (pin "2") (pinfunction "2_2") (pintype "passive"))
    )
    (net (code "48") (name "Net-(Q10-D)") (class "Default")
      (node (ref "LED1") (pin "C") (pinfunction "C_C") (pintype "passive"))
      (node (ref "LED2") (pin "C") (pinfunction "C_C") (pintype "passive"))
      (node (ref "LED3") (pin "C") (pinfunction "C_C") (pintype "passive"))
      (node (ref "LED4") (pin "C") (pinfunction "C_C") (pintype "passive"))
      (node (ref "Q10") (pin "3") (pinfunction "D_3") (pintype "passive"))
    )
    (net (code "49") (name "Net-(S1-S)") (class "Default")
      (node (ref "R24") (pin "1") (pinfunction "1_1") (pintype "passive"))
      (node (ref "S1") (pin "3") (pinfunction "S_3") (pintype "passive"))
      (node (ref "S1") (pin "4") (pinfunction "S1_4") (pintype "passive"))
    )
    (net (code "50") (name "Net-(S2-S)") (class "Default")
      (node (ref "R22") (pin "1") (pinfunction "1_1") (pintype "passive"))
      (node (ref "S2") (pin "3") (pinfunction "S_3") (pintype "passive"))
      (node (ref "S2") (pin "4") (pinfunction "S1_4") (pintype "passive"))
    )
    (net (code "51") (name "Net-(T1-B)") (class "Default")
      (node (ref "R16") (pin "2") (pinfunction "2_2") (pintype "passive"))
      (node (ref "T1") (pin "1") (pinfunction "B_1") (pintype "passive"))
      (node (ref "T2") (pin "2") (pinfunction "E_2") (pintype "passive"))
    )
    (net (code "52") (name "Net-(T1-C)") (class "Default")
      (node (ref "R17") (pin "1") (pinfunction "1_1") (pintype "passive"))
      (node (ref "T1") (pin "3") (pinfunction "C_3") (pintype "passive"))
      (node (ref "T2") (pin "1") (pinfunction "B_1") (pintype "passive"))
    )
    (net (code "53") (name "SCL") (class "Default")
      (node (ref "IC16") (pin "28") (pinfunction "PC5(ADC5/PTCY/SCL0)_28") (pintype "bidirectional"))
      (node (ref "IC2") (pin "4") (pinfunction "SCL_4") (pintype "open_collector"))
      (node (ref "R11") (pin "1") (pinfunction "1_1") (pintype "passive"))
      (node (ref "X9") (pin "3") (pinfunction "3_3") (pintype "passive"))
    )
    (net (code "54") (name "SDA") (class "Default")
      (node (ref "IC16") (pin "27") (pinfunction "PC4(ADC4/PTCY/SDA0)_27") (pintype "bidirectional"))
      (node (ref "IC2") (pin "5") (pinfunction "SDA_5") (pintype "open_collector"))
      (node (ref "R10") (pin "1") (pinfunction "1_1") (pintype "passive"))
      (node (ref "X9") (pin "4") (pinfunction "4_4") (pintype "passive"))
    )
    (net (code "55") (name "UART_GP{slash}SCK") (class "Default")
      (node (ref "IC16") (pin "17") (pinfunction "PB5(PTCXY/XCK1/SCK0)_17") (pintype "bidirectional"))
      (node (ref "TP3") (pin "TP") (pinfunction "TP_TP") (pintype "input"))
      (node (ref "X8") (pin "2") (pinfunction "2_2") (pintype "passive"))
      (node (ref "X9") (pin "2") (pinfunction "2_2") (pintype "passive"))
    )
    (net (code "56") (name "UART_RX{slash}MISO") (class "Default")
      (node (ref "D11") (pin "1") (pinfunction "1_1") (pintype "passive"))
      (node (ref "IC16") (pin "16") (pinfunction "PB4(MISO0/RXD1/PTCXY)_16") (pintype "bidirectional"))
      (node (ref "TP4") (pin "TP") (pinfunction "TP_TP") (pintype "input"))
      (node (ref "X8") (pin "4") (pinfunction "4_4") (pintype "passive"))
    )
    (net (code "57") (name "UART_TX{slash}MOSI") (class "Default")
      (node (ref "D11") (pin "2") (pinfunction "2_2") (pintype "passive"))
      (node (ref "IC16") (pin "15") (pinfunction "PB3(MOSI0/TXD1/OC2A/PTCXY)_15") (pintype "bidirectional"))
      (node (ref "TP5") (pin "TP") (pinfunction "TP_TP") (pintype "input"))
      (node (ref "X8") (pin "3") (pinfunction "3_3") (pintype "passive"))
    )
    (net (code "58") (name "USB1_D_N") (class "Default")
      (node (ref "IC1") (pin "2") (pinfunction "1D-_2") (pintype "passive"))
      (node (ref "X3") (pin "2") (pinfunction "2_2") (pintype "input"))
    )
    (net (code "59") (name "USB1_D_P") (class "Default")
      (node (ref "IC1") (pin "1") (pinfunction "1D+_1") (pintype "passive"))
      (node (ref "X3") (pin "3") (pinfunction "3_3") (pintype "input"))
    )
    (net (code "60") (name "USB1_VBUS") (class "Default")
      (node (ref "D1") (pin "2") (pinfunction "A2_2") (pintype "passive"))
      (node (ref "D5") (pin "2") (pinfunction "2_2") (pintype "passive"))
      (node (ref "Q5") (pin "3") (pinfunction "D_3") (pintype "passive"))
      (node (ref "R12") (pin "2") (pinfunction "2_2") (pintype "passive"))
      (node (ref "R19") (pin "1") (pinfunction "1_1") (pintype "passive"))
      (node (ref "X3") (pin "1") (pinfunction "1_1") (pintype "input"))
    )
    (net (code "61") (name "USB1_VBUS_EN") (class "Default")
      (node (ref "IC16") (pin "22") (pinfunction "PE3(ADC7/PTCY/T3/MOSI1)_22") (pintype "bidirectional"))
      (node (ref "Q6") (pin "1") (pinfunction "G_1") (pintype "passive"))
      (node (ref "R31") (pin "2") (pinfunction "2_2") (pintype "passive"))
    )
    (net (code "62") (name "USB1_VBUS_MEAS") (class "Default")
      (node (ref "C12") (pin "1") (pinfunction "1_1") (pintype "passive"))
      (node (ref "IC16") (pin "23") (pinfunction "PC0(ADC0/PTCY/MISO1)_23") (pintype "bidirectional"))
      (node (ref "R12") (pin "1") (pinfunction "1_1") (pintype "passive"))
      (node (ref "R13") (pin "2") (pinfunction "2_2") (pintype "passive"))
    )
    (net (code "63") (name "USB2_D_N") (class "Default")
      (node (ref "IC1") (pin "4") (pinfunction "2D-_4") (pintype "passive"))
      (node (ref "X2") (pin "2") (pinfunction "2_2") (pintype "input"))
    )
    (net (code "64") (name "USB2_D_P") (class "Default")
      (node (ref "IC1") (pin "3") (pinfunction "2D+_3") (pintype "passive"))
      (node (ref "X2") (pin "3") (pinfunction "3_3") (pintype "input"))
    )
    (net (code "65") (name "USB2_VBUS") (class "Default")
      (node (ref "D1") (pin "1") (pinfunction "A1_1") (pintype "passive"))
      (node (ref "D6") (pin "2") (pinfunction "2_2") (pintype "passive"))
      (node (ref "Q2") (pin "3") (pinfunction "D_3") (pintype "passive"))
      (node (ref "R14") (pin "2") (pinfunction "2_2") (pintype "passive"))
      (node (ref "R20") (pin "1") (pinfunction "1_1") (pintype "passive"))
      (node (ref "X2") (pin "1") (pinfunction "1_1") (pintype "input"))
    )
    (net (code "66") (name "USB2_VBUS_EN") (class "Default")
      (node (ref "IC16") (pin "19") (pinfunction "PE2(ADC6/PTCY/ICP3/SS1)_19") (pintype "bidirectional"))
      (node (ref "Q3") (pin "1") (pinfunction "G_1") (pintype "passive"))
      (node (ref "R32") (pin "2") (pinfunction "2_2") (pintype "passive"))
    )
    (net (code "67") (name "USB2_VBUS_MEAS") (class "Default")
      (node (ref "C13") (pin "1") (pinfunction "1_1") (pintype "passive"))
      (node (ref "IC16") (pin "24") (pinfunction "PC1(ADC1/PTCY/SCK1)_24") (pintype "bidirectional"))
      (node (ref "R14") (pin "1") (pinfunction "1_1") (pintype "passive"))
      (node (ref "R15") (pin "2") (pinfunction "2_2") (pintype "passive"))
    )
    (net (code "68") (name "USBCTRL_D_N") (class "Default")
      (node (ref "R44") (pin "2") (pinfunction "2_2") (pintype "passive"))
      (node (ref "R46") (pin "1") (pinfunction "1_1") (pintype "passive"))
      (node (ref "X7") (pin "2") (pinfunction "2_2") (pintype "input"))
    )
    (net (code "69") (name "USBCTRL_D_P") (class "Default")
      (node (ref "R45") (pin "2") (pinfunction "2_2") (pintype "passive"))
      (node (ref "X7") (pin "3") (pinfunction "3_3") (pintype "input"))
    )
    (net (code "70") (name "USBCTRL_VBUS") (class "Default")
      (node (ref "D2") (pin "1") (pinfunction "A1_1") (pintype "passive"))
      (node (ref "D2") (pin "2") (pinfunction "A2_2") (pintype "passive"))
      (node (ref "X7") (pin "1") (pinfunction "1_1") (pintype "input"))
    )
    (net (code "71") (name "USBO_D_N") (class "Default")
      (node (ref "IC1") (pin "7") (pinfunction "D-_7") (pintype "passive"))
      (node (ref "X1") (pin "2") (pinfunction "2_2") (pintype "passive"))
    )
    (net (code "72") (name "USBO_D_P") (class "Default")
      (node (ref "IC1") (pin "8") (pinfunction "D+_8") (pintype "passive"))
      (node (ref "X1") (pin "3") (pinfunction "3_3") (pintype "passive"))
    )
    (net (code "73") (name "USBO_SENSE_N") (class "Default")
      (node (ref "C2") (pin "1") (pinfunction "1_1") (pintype "passive"))
      (node (ref "IC2") (pin "14") (pinfunction "SENSE2-_14") (pintype "input"))
      (node (ref "R6") (pin "1") (pinfunction "1_1") (pintype "passive"))
    )
    (net (code "74") (name "USBO_SENSE_P") (class "Default")
      (node (ref "C2") (pin "2") (pinfunction "2_2") (pintype "passive"))
      (node (ref "C9") (pin "2") (pinfunction "2_2") (pintype "passive"))
      (node (ref "IC2") (pin "13") (pinfunction "SENSE2+_13") (pintype "input"))
      (node (ref "R4") (pin "1") (pinfunction "1_1") (pintype "passive"))
    )
    (net (code "75") (name "USBO_VBUS_SW") (class "Default")
      (node (ref "Q1") (pin "3") (pinfunction "D_3") (pintype "passive"))
      (node (ref "Q4") (pin "3") (pinfunction "D_3") (pintype "passive"))
      (node (ref "R4") (pin "2") (pinfunction "2_2") (pintype "passive"))
      (node (ref "R5") (pin "1") (pinfunction "1_1") (pintype "passive"))
    )
    (net (code "76") (name "VBUS_OUT") (class "Default")
      (node (ref "D7") (pin "2") (pinfunction "2_2") (pintype "passive"))
      (node (ref "R5") (pin "2") (pinfunction "2_2") (pintype "passive"))
      (node (ref "R6") (pin "2") (pinfunction "2_2") (pintype "passive"))
      (node (ref "X1") (pin "1") (pinfunction "1_1") (pintype "passive"))
    )
    (net (code "77") (name "unconnected-(IC16-PE0(SDA1{slash}ICP4{slash}ACO{slash}PTCXY)-Pad3)") (class "Default")
      (node (ref "IC16") (pin "3") (pinfunction "PE0(SDA1/ICP4/ACO/PTCXY)_3") (pintype "bidirectional"))
    )
    (net (code "78") (name "unconnected-(X2-Pad4)") (class "Default")
      (node (ref "X2") (pin "4") (pinfunction "4_4") (pintype "input"))
    )
    (net (code "79") (name "unconnected-(X3-Pad4)") (class "Default")
      (node (ref "X3") (pin "4") (pinfunction "4_4") (pintype "input"))
    )
    (net (code "80") (name "unconnected-(X7-Pad4)") (class "Default")
      (node (ref "X7") (pin "4") (pinfunction "4_4") (pintype "input"))
    )
  )
)
